# F3DroneV4.net
KiCad netlist of a schematic drawn in Altium Designer
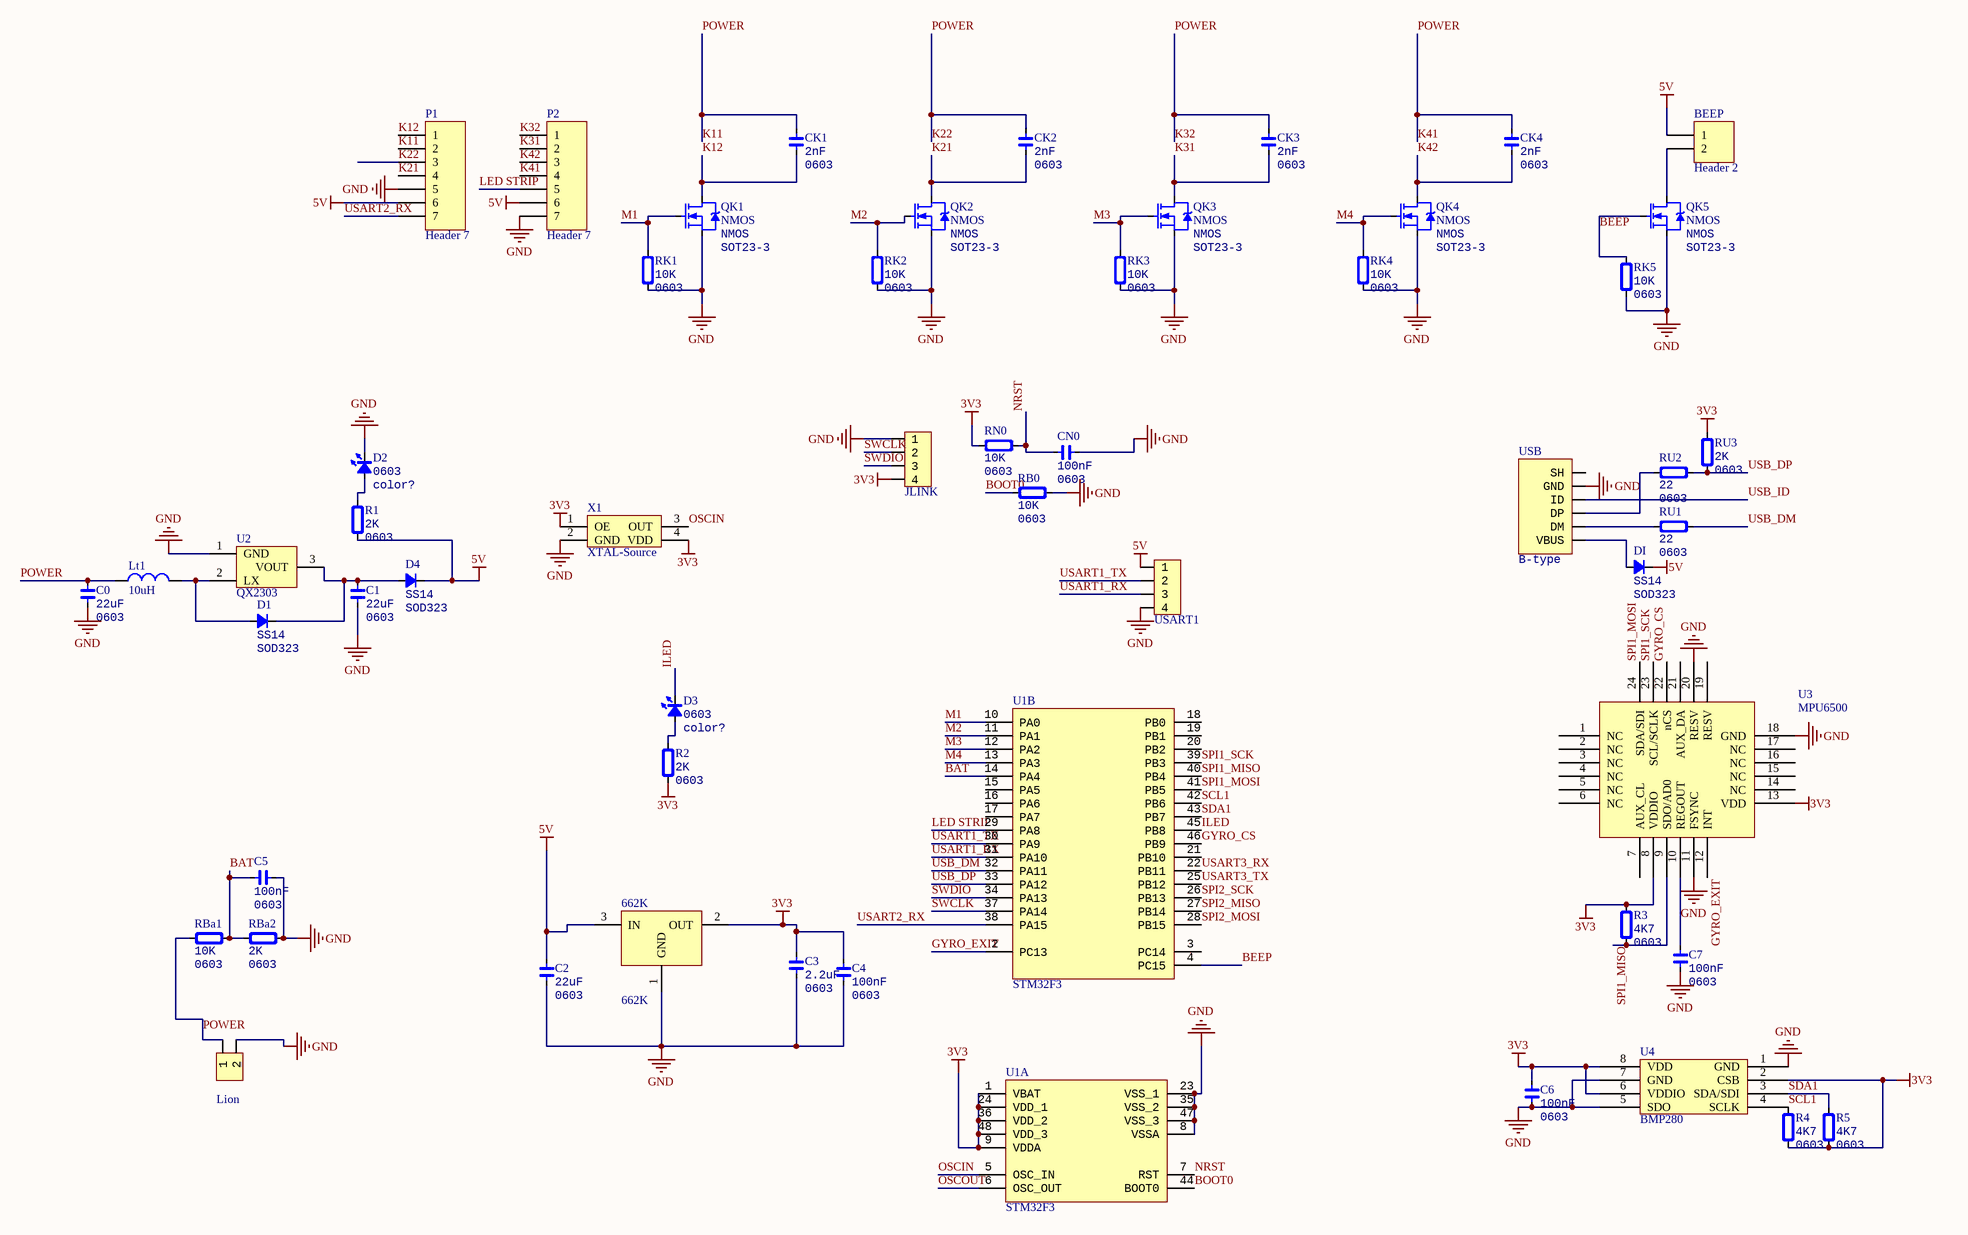
[diagram p0: F3DroneV4.SchDoc]

(export (version "E")
  (design (tool "Eeschema 10.0.6"))
  (components
    (comp (ref "662K") (value "662K") (footprint "SOT-23") (libsource (lib "PPD") (part "662K")))
    (comp (ref "BEEP")
      (value "Header 2")
      (footprint "HDR1X2")
      (description "Header, 2-Pin")
      (fields (field (name "PUBLISHER") "Altium Limited"))
      (libsource (lib "Miscellaneous Connectors") (part "Header 2"))
    )
    (comp (ref "C0")
      (value "22uF")
      (footprint "CAP_0603")
      (description "Capacitor")
      (fields (field (name "TYPE") "0603") (field (name "Comment") "C0603"))
      (libsource (lib "Integrated_Library") (part "Cap_0603"))
    )
    (comp (ref "C1")
      (value "22uF")
      (footprint "CAP_0603")
      (description "Capacitor")
      (fields (field (name "TYPE") "0603") (field (name "Comment") "C0603"))
      (libsource (lib "Integrated_Library") (part "Cap_0603"))
    )
    (comp (ref "C2")
      (value "22uF")
      (footprint "CAP_0603")
      (description "Capacitor")
      (fields (field (name "TYPE") "0603") (field (name "Comment") "C0603"))
      (libsource (lib "Integrated_Library") (part "Cap_0603"))
    )
    (comp (ref "C3")
      (value "2.2uF")
      (footprint "CAP_0603")
      (description "Capacitor")
      (fields (field (name "TYPE") "0603") (field (name "Comment") "C0603"))
      (libsource (lib "Integrated_Library") (part "Cap_0603"))
    )
    (comp (ref "C4")
      (value "100nF")
      (footprint "CAP_0603")
      (description "Capacitor")
      (fields (field (name "TYPE") "0603") (field (name "Comment") "C0603"))
      (libsource (lib "Integrated_Library") (part "Cap_0603"))
    )
    (comp (ref "C5")
      (value "100nF")
      (footprint "CAP_0603")
      (description "Capacitor")
      (fields (field (name "TYPE") "0603") (field (name "Comment") "C0603"))
      (libsource (lib "") (part "Cap_0603_1"))
    )
    (comp (ref "C6")
      (value "100nF")
      (footprint "CAP_0603")
      (description "Capacitor")
      (fields (field (name "TYPE") "0603") (field (name "Comment") "C0603"))
      (libsource (lib "") (part "Cap_0603_2"))
    )
    (comp (ref "C7")
      (value "100nF")
      (footprint "CAP_0603")
      (description "Capacitor")
      (fields (field (name "TYPE") "0603") (field (name "Comment") "C0603"))
      (libsource (lib "") (part "Cap_0603_2"))
    )
    (comp (ref "CK1")
      (value "2nF")
      (footprint "CAP_0603")
      (description "Capacitor")
      (fields (field (name "TYPE") "0603") (field (name "Comment") "C0603"))
      (libsource (lib "Integrated_Library") (part "Cap_0603"))
    )
    (comp (ref "CK2")
      (value "2nF")
      (footprint "CAP_0603")
      (description "Capacitor")
      (fields (field (name "TYPE") "0603") (field (name "Comment") "C0603"))
      (libsource (lib "Integrated_Library") (part "Cap_0603"))
    )
    (comp (ref "CK3")
      (value "2nF")
      (footprint "CAP_0603")
      (description "Capacitor")
      (fields (field (name "TYPE") "0603") (field (name "Comment") "C0603"))
      (libsource (lib "Integrated_Library") (part "Cap_0603"))
    )
    (comp (ref "CK4")
      (value "2nF")
      (footprint "CAP_0603")
      (description "Capacitor")
      (fields (field (name "TYPE") "0603") (field (name "Comment") "C0603"))
      (libsource (lib "Integrated_Library") (part "Cap_0603"))
    )
    (comp (ref "CN0")
      (value "100nF")
      (footprint "CAP_0603")
      (description "Capacitor")
      (fields (field (name "TYPE") "0603") (field (name "Comment") "C0603"))
      (libsource (lib "") (part "Cap_0603_1"))
    )
    (comp (ref "D1")
      (value "SS14")
      (footprint "SOD-323")
      (description "Diode")
      (fields (field (name "TYPE") "SOD323"))
      (libsource (lib "Integrated_Library") (part "Diode_SOD323"))
    )
    (comp (ref "D2")
      (value "color?")
      (footprint "LED_0603_BLUE")
      (description "LED")
      (fields (field (name "TYPE") "0603"))
      (libsource (lib "Integrated_Library") (part "LED_0603"))
    )
    (comp (ref "D3")
      (value "color?")
      (footprint "LED_0603_BLUE")
      (description "LED")
      (fields (field (name "TYPE") "0603"))
      (libsource (lib "Integrated_Library") (part "LED_0603"))
    )
    (comp (ref "D4")
      (value "SS14")
      (footprint "SOD-323")
      (description "Diode")
      (fields (field (name "TYPE") "SOD323"))
      (libsource (lib "Integrated_Library") (part "Diode_SOD323"))
    )
    (comp (ref "DI")
      (value "SS14")
      (footprint "SOD-323")
      (description "Diode")
      (fields (field (name "TYPE") "SOD323"))
      (libsource (lib "Integrated_Library") (part "Diode_SOD323"))
    )
    (comp (ref "JLINK")
      (value "HDR1x4_1.27")
      (footprint "HDR1X4_1.27_180")
      (description "Header")
      (libsource (lib "Integrated_Library") (part "HDR1x4_1.27"))
    )
    (comp (ref "Lion")
      (value "HDR1x2_1.27T")
      (footprint "HDR1X2_1.27_180")
      (description "Header")
      (libsource (lib "Integrated_Library") (part "HDR1x2_1.27T"))
    )
    (comp (ref "Lt1")
      (value "10uH")
      (footprint "0420")
      (description "电感")
      (fields (field (name "Comment") "Inductor") (field (name "PUBLISHER") "Altium Limited"))
      (libsource (lib "PPD") (part "Inductor"))
    )
    (comp (ref "P1")
      (value "Header 7")
      (footprint "HDR1X7")
      (description "Header, 7-Pin")
      (fields (field (name "PUBLISHER") "Altium Limited"))
      (libsource (lib "Miscellaneous Connectors") (part "Header 7"))
    )
    (comp (ref "P2")
      (value "Header 7")
      (footprint "HDR1X7")
      (description "Header, 7-Pin")
      (fields (field (name "PUBLISHER") "Altium Limited"))
      (libsource (lib "Miscellaneous Connectors") (part "Header 7"))
    )
    (comp (ref "QK1")
      (value "NMOS")
      (footprint "SOT23-3")
      (description "MOSFET")
      (fields (field (name "ALTIUM_VALUE") "NMOS") (field (name "TYPE") "SOT23-3"))
      (libsource (lib "Integrated_Library") (part "MOSFET_N_SOT23"))
    )
    (comp (ref "QK2")
      (value "NMOS")
      (footprint "SOT23-3")
      (description "MOSFET")
      (fields (field (name "ALTIUM_VALUE") "NMOS") (field (name "TYPE") "SOT23-3"))
      (libsource (lib "Integrated_Library") (part "MOSFET_N_SOT23"))
    )
    (comp (ref "QK3")
      (value "NMOS")
      (footprint "SOT23-3")
      (description "MOSFET")
      (fields (field (name "ALTIUM_VALUE") "NMOS") (field (name "TYPE") "SOT23-3"))
      (libsource (lib "Integrated_Library") (part "MOSFET_N_SOT23"))
    )
    (comp (ref "QK4")
      (value "NMOS")
      (footprint "SOT23-3")
      (description "MOSFET")
      (fields (field (name "ALTIUM_VALUE") "NMOS") (field (name "TYPE") "SOT23-3"))
      (libsource (lib "Integrated_Library") (part "MOSFET_N_SOT23"))
    )
    (comp (ref "QK5")
      (value "NMOS")
      (footprint "SOT23-3")
      (description "MOSFET")
      (fields (field (name "ALTIUM_VALUE") "NMOS") (field (name "TYPE") "SOT23-3"))
      (libsource (lib "Integrated_Library") (part "MOSFET_N_SOT23"))
    )
    (comp (ref "R1")
      (value "2K")
      (footprint "RES_0603")
      (description "Resistor")
      (fields (field (name "TYPE") "0603") (field (name "Comment") "R0603"))
      (libsource (lib "Integrated_Library") (part "Res_0603"))
    )
    (comp (ref "R2")
      (value "2K")
      (footprint "RES_0603")
      (description "Resistor")
      (fields (field (name "TYPE") "0603") (field (name "Comment") "R0603"))
      (libsource (lib "Integrated_Library") (part "Res_0603"))
    )
    (comp (ref "R3")
      (value "4K7")
      (footprint "RES_0603")
      (description "Resistor")
      (fields (field (name "TYPE") "0603") (field (name "Comment") "R0603"))
      (libsource (lib "Integrated_Library") (part "Res_0603"))
    )
    (comp (ref "R4")
      (value "4K7")
      (footprint "RES_0603")
      (description "Resistor")
      (fields (field (name "TYPE") "0603") (field (name "Comment") "R0603"))
      (libsource (lib "Integrated_Library") (part "Res_0603"))
    )
    (comp (ref "R5")
      (value "4K7")
      (footprint "RES_0603")
      (description "Resistor")
      (fields (field (name "TYPE") "0603") (field (name "Comment") "R0603"))
      (libsource (lib "Integrated_Library") (part "Res_0603"))
    )
    (comp (ref "RB0")
      (value "10K")
      (footprint "RES_0603")
      (description "Resistor")
      (fields (field (name "TYPE") "0603") (field (name "Comment") "R0603"))
      (libsource (lib "Integrated_Library") (part "Res_0603"))
    )
    (comp (ref "RBa1")
      (value "10K")
      (footprint "RES_0603")
      (description "Resistor")
      (fields (field (name "TYPE") "0603") (field (name "Comment") "R0603"))
      (libsource (lib "Integrated_Library") (part "Res_0603"))
    )
    (comp (ref "RBa2")
      (value "2K")
      (footprint "RES_0603")
      (description "Resistor")
      (fields (field (name "TYPE") "0603") (field (name "Comment") "R0603"))
      (libsource (lib "Integrated_Library") (part "Res_0603"))
    )
    (comp (ref "RK1")
      (value "10K")
      (footprint "RES_0603")
      (description "Resistor")
      (fields (field (name "TYPE") "0603") (field (name "Comment") "R0603"))
      (libsource (lib "Integrated_Library") (part "Res_0603"))
    )
    (comp (ref "RK2")
      (value "10K")
      (footprint "RES_0603")
      (description "Resistor")
      (fields (field (name "TYPE") "0603") (field (name "Comment") "R0603"))
      (libsource (lib "Integrated_Library") (part "Res_0603"))
    )
    (comp (ref "RK3")
      (value "10K")
      (footprint "RES_0603")
      (description "Resistor")
      (fields (field (name "TYPE") "0603") (field (name "Comment") "R0603"))
      (libsource (lib "Integrated_Library") (part "Res_0603"))
    )
    (comp (ref "RK4")
      (value "10K")
      (footprint "RES_0603")
      (description "Resistor")
      (fields (field (name "TYPE") "0603") (field (name "Comment") "R0603"))
      (libsource (lib "Integrated_Library") (part "Res_0603"))
    )
    (comp (ref "RK5")
      (value "10K")
      (footprint "RES_0603")
      (description "Resistor")
      (fields (field (name "TYPE") "0603") (field (name "Comment") "R0603"))
      (libsource (lib "Integrated_Library") (part "Res_0603"))
    )
    (comp (ref "RN0")
      (value "10K")
      (footprint "RES_0603")
      (description "Resistor")
      (fields (field (name "TYPE") "0603") (field (name "Comment") "R0603"))
      (libsource (lib "Integrated_Library") (part "Res_0603"))
    )
    (comp (ref "RU1")
      (value "22")
      (footprint "RES_0603")
      (description "Resistor")
      (fields (field (name "TYPE") "0603") (field (name "Comment") "R0603"))
      (libsource (lib "Integrated_Library") (part "Res_0603"))
    )
    (comp (ref "RU2")
      (value "22")
      (footprint "RES_0603")
      (description "Resistor")
      (fields (field (name "TYPE") "0603") (field (name "Comment") "R0603"))
      (libsource (lib "Integrated_Library") (part "Res_0603"))
    )
    (comp (ref "RU3")
      (value "2K")
      (footprint "RES_0603")
      (description "Resistor")
      (fields (field (name "TYPE") "0603") (field (name "Comment") "R0603"))
      (libsource (lib "Integrated_Library") (part "Res_0603"))
    )
    (comp (ref "U1")
      (value "STM32F3")
      (footprint "LQFP_P0.5_48")
      (description "MCU")
      (libsource (lib "Integrated_Library") (part "STM32F303C"))
    )
    (comp (ref "U2") (value "QX2303") (footprint "SOT-23") (libsource (lib "PPD") (part "QX2303")))
    (comp (ref "U3")
      (value "MPU6500")
      (footprint "QFN40P300X300X90_HS-25N")
      (libsource (lib "PPD") (part "MPU6500"))
    )
    (comp (ref "U4") (value "BMP280") (footprint "BMP280") (libsource (lib "PPD") (part "BMP280")))
    (comp (ref "USART1")
      (value "HDR1x4_1.27")
      (footprint "HDR1X4_1.27_180")
      (description "Header")
      (libsource (lib "Integrated_Library") (part "HDR1x4_1.27"))
    )
    (comp (ref "USB")
      (value "MicroUSB")
      (footprint "USB_Micro-AB")
      (description "USB")
      (fields (field (name "TYPE") "B-type"))
      (libsource (lib "Integrated_Library") (part "USB_Micro"))
    )
    (comp (ref "X1")
      (value "XTAL-Source")
      (footprint "XTAL_3225")
      (libsource (lib "PPD") (part "XTAL-Source"))
    )
  )
  (nets
    (net (code "1") (name "/BAT") (class "Default")
      (node (ref "C5") (pin "2") (pinfunction "2_2") (pintype "passive"))
      (node (ref "RBa1") (pin "1") (pinfunction "1_1") (pintype "passive"))
      (node (ref "RBa2") (pin "2") (pinfunction "2_2") (pintype "passive"))
      (node (ref "U1") (pin "14") (pinfunction "PA4_14") (pintype "passive"))
    )
    (net (code "2") (name "/BEEP") (class "Default")
      (node (ref "QK5") (pin "1") (pinfunction "G_1") (pintype "passive"))
      (node (ref "RK5") (pin "2") (pinfunction "2_2") (pintype "passive"))
      (node (ref "U1") (pin "4") (pinfunction "PC15_4") (pintype "passive"))
    )
    (net (code "3") (name "/BOOT0") (class "Default")
      (node (ref "RB0") (pin "2") (pinfunction "2_2") (pintype "passive"))
      (node (ref "U1") (pin "44") (pinfunction "BOOT0_44") (pintype "passive"))
    )
    (net (code "4") (name "/GYRO_CS") (class "Default")
      (node (ref "U1") (pin "46") (pinfunction "PB9_46") (pintype "passive"))
      (node (ref "U3") (pin "22") (pinfunction "nCS_22") (pintype "passive"))
    )
    (net (code "5") (name "/GYRO_EXIT") (class "Default")
      (node (ref "U1") (pin "2") (pinfunction "PC13_2") (pintype "passive"))
      (node (ref "U3") (pin "12") (pinfunction "INT_12") (pintype "passive"))
    )
    (net (code "6") (name "/ILED") (class "Default")
      (node (ref "D3") (pin "2") (pinfunction "K_2") (pintype "passive"))
      (node (ref "U1") (pin "45") (pinfunction "PB8_45") (pintype "passive"))
    )
    (net (code "7") (name "/K11") (class "Default")
      (node (ref "C0") (pin "2") (pinfunction "2_2") (pintype "passive"))
      (node (ref "CK1") (pin "2") (pinfunction "2_2") (pintype "passive"))
      (node (ref "CK2") (pin "2") (pinfunction "2_2") (pintype "passive"))
      (node (ref "CK3") (pin "2") (pinfunction "2_2") (pintype "passive"))
      (node (ref "CK4") (pin "2") (pinfunction "2_2") (pintype "passive"))
      (node (ref "Lion") (pin "1") (pinfunction "1_1") (pintype "passive"))
      (node (ref "Lt1") (pin "1") (pinfunction "1_1") (pintype "passive"))
      (node (ref "P1") (pin "2") (pinfunction "2_2") (pintype "passive"))
      (node (ref "P1") (pin "3") (pinfunction "3_3") (pintype "passive"))
      (node (ref "P2") (pin "1") (pinfunction "1_1") (pintype "passive"))
      (node (ref "P2") (pin "4") (pinfunction "4_4") (pintype "passive"))
      (node (ref "RBa1") (pin "2") (pinfunction "2_2") (pintype "passive"))
    )
    (net (code "8") (name "/K12") (class "Default")
      (node (ref "CK1") (pin "1") (pinfunction "1_1") (pintype "passive"))
      (node (ref "P1") (pin "1") (pinfunction "1_1") (pintype "passive"))
      (node (ref "QK1") (pin "3") (pinfunction "D_3") (pintype "passive"))
    )
    (net (code "9") (name "/K21") (class "Default")
      (node (ref "CK2") (pin "1") (pinfunction "1_1") (pintype "passive"))
      (node (ref "P1") (pin "4") (pinfunction "4_4") (pintype "passive"))
      (node (ref "QK2") (pin "3") (pinfunction "D_3") (pintype "passive"))
    )
    (net (code "10") (name "/K31") (class "Default")
      (node (ref "CK3") (pin "1") (pinfunction "1_1") (pintype "passive"))
      (node (ref "P2") (pin "2") (pinfunction "2_2") (pintype "passive"))
      (node (ref "QK3") (pin "3") (pinfunction "D_3") (pintype "passive"))
    )
    (net (code "11") (name "/K42") (class "Default")
      (node (ref "CK4") (pin "1") (pinfunction "1_1") (pintype "passive"))
      (node (ref "P2") (pin "3") (pinfunction "3_3") (pintype "passive"))
      (node (ref "QK4") (pin "3") (pinfunction "D_3") (pintype "passive"))
    )
    (net (code "12") (name "/LED STRIP") (class "Default")
      (node (ref "P2") (pin "5") (pinfunction "5_5") (pintype "passive"))
      (node (ref "U1") (pin "29") (pinfunction "PA8_29") (pintype "passive"))
    )
    (net (code "13") (name "/M1") (class "Default")
      (node (ref "QK1") (pin "1") (pinfunction "G_1") (pintype "passive"))
      (node (ref "RK1") (pin "2") (pinfunction "2_2") (pintype "passive"))
      (node (ref "U1") (pin "10") (pinfunction "PA0_10") (pintype "passive"))
    )
    (net (code "14") (name "/M2") (class "Default")
      (node (ref "QK2") (pin "1") (pinfunction "G_1") (pintype "passive"))
      (node (ref "RK2") (pin "2") (pinfunction "2_2") (pintype "passive"))
      (node (ref "U1") (pin "11") (pinfunction "PA1_11") (pintype "passive"))
    )
    (net (code "15") (name "/M3") (class "Default")
      (node (ref "QK3") (pin "1") (pinfunction "G_1") (pintype "passive"))
      (node (ref "RK3") (pin "2") (pinfunction "2_2") (pintype "passive"))
      (node (ref "U1") (pin "12") (pinfunction "PA2_12") (pintype "passive"))
    )
    (net (code "16") (name "/M4") (class "Default")
      (node (ref "QK4") (pin "1") (pinfunction "G_1") (pintype "passive"))
      (node (ref "RK4") (pin "2") (pinfunction "2_2") (pintype "passive"))
      (node (ref "U1") (pin "13") (pinfunction "PA3_13") (pintype "passive"))
    )
    (net (code "17") (name "/NRST") (class "Default")
      (node (ref "CN0") (pin "2") (pinfunction "2_2") (pintype "passive"))
      (node (ref "RN0") (pin "1") (pinfunction "1_1") (pintype "passive"))
      (node (ref "U1") (pin "7") (pinfunction "RST_7") (pintype "passive"))
    )
    (net (code "18") (name "/OSCIN") (class "Default")
      (node (ref "U1") (pin "5") (pinfunction "OSC_IN_5") (pintype "passive"))
      (node (ref "X1") (pin "3") (pinfunction "OUT_3") (pintype "passive"))
    )
    (net (code "19") (name "/OSCOUT") (class "Default")
      (node (ref "U1") (pin "6") (pinfunction "OSC_OUT_6") (pintype "passive"))
    )
    (net (code "20") (name "/SCL1") (class "Default")
      (node (ref "R4") (pin "2") (pinfunction "2_2") (pintype "passive"))
      (node (ref "U1") (pin "42") (pinfunction "PB6_42") (pintype "passive"))
      (node (ref "U4") (pin "4") (pinfunction "SCLK_4") (pintype "passive"))
    )
    (net (code "21") (name "/SDA1") (class "Default")
      (node (ref "R5") (pin "2") (pinfunction "2_2") (pintype "passive"))
      (node (ref "U1") (pin "43") (pinfunction "PB7_43") (pintype "passive"))
      (node (ref "U4") (pin "3") (pinfunction "SDA/SDI_3") (pintype "passive"))
    )
    (net (code "22") (name "/SPI1_MISO") (class "Default")
      (node (ref "R3") (pin "1") (pinfunction "1_1") (pintype "passive"))
      (node (ref "U1") (pin "40") (pinfunction "PB4_40") (pintype "passive"))
      (node (ref "U3") (pin "9") (pinfunction "SDO/AD0_9") (pintype "passive"))
    )
    (net (code "23") (name "/SPI1_MOSI") (class "Default")
      (node (ref "U1") (pin "41") (pinfunction "PB5_41") (pintype "passive"))
      (node (ref "U3") (pin "24") (pinfunction "SDA/SDI_24") (pintype "passive"))
    )
    (net (code "24") (name "/SPI1_SCK") (class "Default")
      (node (ref "U1") (pin "39") (pinfunction "PB3_39") (pintype "passive"))
      (node (ref "U3") (pin "23") (pinfunction "SCL/SCLK_23") (pintype "passive"))
    )
    (net (code "25") (name "/SPI2_MISO") (class "Default")
      (node (ref "U1") (pin "27") (pinfunction "PB14_27") (pintype "passive"))
    )
    (net (code "26") (name "/SPI2_MOSI") (class "Default")
      (node (ref "U1") (pin "28") (pinfunction "PB15_28") (pintype "passive"))
    )
    (net (code "27") (name "/SPI2_SCK") (class "Default")
      (node (ref "U1") (pin "26") (pinfunction "PB13_26") (pintype "passive"))
    )
    (net (code "28") (name "/SWCLK") (class "Default")
      (node (ref "JLINK") (pin "2") (pinfunction "2_2") (pintype "passive"))
      (node (ref "U1") (pin "37") (pinfunction "PA14_37") (pintype "passive"))
    )
    (net (code "29") (name "/SWDIO") (class "Default")
      (node (ref "JLINK") (pin "3") (pinfunction "3_3") (pintype "passive"))
      (node (ref "U1") (pin "34") (pinfunction "PA13_34") (pintype "passive"))
    )
    (net (code "30") (name "/USART1_RX") (class "Default")
      (node (ref "U1") (pin "31") (pinfunction "PA10_31") (pintype "passive"))
      (node (ref "USART1") (pin "3") (pinfunction "3_3") (pintype "passive"))
    )
    (net (code "31") (name "/USART1_TX") (class "Default")
      (node (ref "U1") (pin "30") (pinfunction "PA9_30") (pintype "passive"))
      (node (ref "USART1") (pin "2") (pinfunction "2_2") (pintype "passive"))
    )
    (net (code "32") (name "/USART2_RX") (class "Default")
      (node (ref "P1") (pin "7") (pinfunction "7_7") (pintype "passive"))
      (node (ref "U1") (pin "38") (pinfunction "PA15_38") (pintype "passive"))
    )
    (net (code "33") (name "/USART3_RX") (class "Default")
      (node (ref "U1") (pin "22") (pinfunction "PB11_22") (pintype "passive"))
    )
    (net (code "34") (name "/USART3_TX") (class "Default")
      (node (ref "U1") (pin "25") (pinfunction "PB12_25") (pintype "passive"))
    )
    (net (code "35") (name "/USB_DM") (class "Default")
      (node (ref "RU1") (pin "1") (pinfunction "1_1") (pintype "passive"))
      (node (ref "U1") (pin "32") (pinfunction "PA11_32") (pintype "passive"))
    )
    (net (code "36") (name "/USB_DP") (class "Default")
      (node (ref "RU2") (pin "1") (pinfunction "1_1") (pintype "passive"))
      (node (ref "RU3") (pin "2") (pinfunction "2_2") (pintype "passive"))
      (node (ref "U1") (pin "33") (pinfunction "PA12_33") (pintype "passive"))
    )
    (net (code "37") (name "/USB_ID") (class "Default")
      (node (ref "USB") (pin "4") (pinfunction "ID_4") (pintype "passive"))
    )
    (net (code "38") (name "3V3") (class "Default")
      (node (ref "662K") (pin "2") (pinfunction "OUT_2") (pintype "passive"))
      (node (ref "C3") (pin "2") (pinfunction "2_2") (pintype "passive"))
      (node (ref "C4") (pin "2") (pinfunction "2_2") (pintype "passive"))
      (node (ref "C6") (pin "1") (pinfunction "1_1") (pintype "passive"))
      (node (ref "JLINK") (pin "4") (pinfunction "4_4") (pintype "passive"))
      (node (ref "R2") (pin "1") (pinfunction "1_1") (pintype "passive"))
      (node (ref "R3") (pin "2") (pinfunction "2_2") (pintype "passive"))
      (node (ref "R4") (pin "1") (pinfunction "1_1") (pintype "passive"))
      (node (ref "R5") (pin "1") (pinfunction "1_1") (pintype "passive"))
      (node (ref "RN0") (pin "2") (pinfunction "2_2") (pintype "passive"))
      (node (ref "RU3") (pin "1") (pinfunction "1_1") (pintype "passive"))
      (node (ref "U1") (pin "1") (pinfunction "VBAT_1") (pintype "passive"))
      (node (ref "U1") (pin "24") (pinfunction "VDD_1_24") (pintype "passive"))
      (node (ref "U1") (pin "36") (pinfunction "VDD_2_36") (pintype "passive"))
      (node (ref "U1") (pin "48") (pinfunction "VDD_3_48") (pintype "passive"))
      (node (ref "U1") (pin "9") (pinfunction "VDDA_9") (pintype "passive"))
      (node (ref "U3") (pin "13") (pinfunction "VDD_13") (pintype "passive"))
      (node (ref "U3") (pin "8") (pinfunction "VDDIO_8") (pintype "passive"))
      (node (ref "U4") (pin "2") (pinfunction "CSB_2") (pintype "passive"))
      (node (ref "U4") (pin "6") (pinfunction "VDDIO_6") (pintype "passive"))
      (node (ref "U4") (pin "8") (pinfunction "VDD_8") (pintype "passive"))
      (node (ref "X1") (pin "1") (pinfunction "OE_1") (pintype "passive"))
      (node (ref "X1") (pin "4") (pinfunction "VDD_4") (pintype "passive"))
    )
    (net (code "39") (name "5V") (class "Default")
      (node (ref "662K") (pin "3") (pinfunction "IN_3") (pintype "passive"))
      (node (ref "BEEP") (pin "1") (pinfunction "1_1") (pintype "passive"))
      (node (ref "C2") (pin "2") (pinfunction "2_2") (pintype "passive"))
      (node (ref "D4") (pin "2") (pinfunction "K_2") (pintype "passive"))
      (node (ref "DI") (pin "2") (pinfunction "K_2") (pintype "passive"))
      (node (ref "P1") (pin "6") (pinfunction "6_6") (pintype "passive"))
      (node (ref "P2") (pin "6") (pinfunction "6_6") (pintype "passive"))
      (node (ref "R1") (pin "1") (pinfunction "1_1") (pintype "passive"))
      (node (ref "USART1") (pin "1") (pinfunction "1_1") (pintype "passive"))
    )
    (net (code "40") (name "GND") (class "Default")
      (node (ref "662K") (pin "1") (pinfunction "GND_1") (pintype "passive"))
      (node (ref "C0") (pin "1") (pinfunction "1_1") (pintype "passive"))
      (node (ref "C1") (pin "1") (pinfunction "1_1") (pintype "passive"))
      (node (ref "C2") (pin "1") (pinfunction "1_1") (pintype "passive"))
      (node (ref "C3") (pin "1") (pinfunction "1_1") (pintype "passive"))
      (node (ref "C4") (pin "1") (pinfunction "1_1") (pintype "passive"))
      (node (ref "C5") (pin "1") (pinfunction "1_1") (pintype "passive"))
      (node (ref "C6") (pin "2") (pinfunction "2_2") (pintype "passive"))
      (node (ref "C7") (pin "2") (pinfunction "2_2") (pintype "passive"))
      (node (ref "CN0") (pin "1") (pinfunction "1_1") (pintype "passive"))
      (node (ref "D2") (pin "2") (pinfunction "K_2") (pintype "passive"))
      (node (ref "JLINK") (pin "1") (pinfunction "1_1") (pintype "passive"))
      (node (ref "Lion") (pin "2") (pinfunction "2_2") (pintype "passive"))
      (node (ref "P1") (pin "5") (pinfunction "5_5") (pintype "passive"))
      (node (ref "P2") (pin "7") (pinfunction "7_7") (pintype "passive"))
      (node (ref "QK1") (pin "2") (pinfunction "S_2") (pintype "passive"))
      (node (ref "QK2") (pin "2") (pinfunction "S_2") (pintype "passive"))
      (node (ref "QK3") (pin "2") (pinfunction "S_2") (pintype "passive"))
      (node (ref "QK4") (pin "2") (pinfunction "S_2") (pintype "passive"))
      (node (ref "QK5") (pin "2") (pinfunction "S_2") (pintype "passive"))
      (node (ref "RB0") (pin "1") (pinfunction "1_1") (pintype "passive"))
      (node (ref "RBa2") (pin "1") (pinfunction "1_1") (pintype "passive"))
      (node (ref "RK1") (pin "1") (pinfunction "1_1") (pintype "passive"))
      (node (ref "RK2") (pin "1") (pinfunction "1_1") (pintype "passive"))
      (node (ref "RK3") (pin "1") (pinfunction "1_1") (pintype "passive"))
      (node (ref "RK4") (pin "1") (pinfunction "1_1") (pintype "passive"))
      (node (ref "RK5") (pin "1") (pinfunction "1_1") (pintype "passive"))
      (node (ref "U1") (pin "23") (pinfunction "VSS_1_23") (pintype "passive"))
      (node (ref "U1") (pin "35") (pinfunction "VSS_2_35") (pintype "passive"))
      (node (ref "U1") (pin "47") (pinfunction "VSS_3_47") (pintype "passive"))
      (node (ref "U1") (pin "8") (pinfunction "VSSA_8") (pintype "passive"))
      (node (ref "U2") (pin "1") (pinfunction "GND_1") (pintype "passive"))
      (node (ref "U3") (pin "11") (pinfunction "FSYNC_11") (pintype "passive"))
      (node (ref "U3") (pin "18") (pinfunction "GND_18") (pintype "passive"))
      (node (ref "U3") (pin "20") (pinfunction "RESV_20") (pintype "passive"))
      (node (ref "U4") (pin "1") (pinfunction "GND_1") (pintype "passive"))
      (node (ref "U4") (pin "5") (pinfunction "SDO_5") (pintype "passive"))
      (node (ref "U4") (pin "7") (pinfunction "GND_7") (pintype "passive"))
      (node (ref "USART1") (pin "4") (pinfunction "4_4") (pintype "passive"))
      (node (ref "USB") (pin "5") (pinfunction "GND_5") (pintype "passive"))
      (node (ref "X1") (pin "2") (pinfunction "GND_2") (pintype "passive"))
    )
    (net (code "41") (name "Net-(D1-A)") (class "Default")
      (node (ref "D1") (pin "1") (pinfunction "A_1") (pintype "passive"))
      (node (ref "Lt1") (pin "2") (pinfunction "2_2") (pintype "passive"))
      (node (ref "U2") (pin "2") (pinfunction "LX_2") (pintype "passive"))
    )
    (net (code "42") (name "Net-(D1-K)") (class "Default")
      (node (ref "C1") (pin "2") (pinfunction "2_2") (pintype "passive"))
      (node (ref "D1") (pin "2") (pinfunction "K_2") (pintype "passive"))
      (node (ref "D4") (pin "1") (pinfunction "A_1") (pintype "passive"))
      (node (ref "U2") (pin "3") (pinfunction "VOUT_3") (pintype "passive"))
    )
    (net (code "43") (name "Net-(D2-A)") (class "Default")
      (node (ref "D2") (pin "1") (pinfunction "A_1") (pintype "passive"))
      (node (ref "R1") (pin "2") (pinfunction "2_2") (pintype "passive"))
    )
    (net (code "44") (name "Net-(D3-A)") (class "Default")
      (node (ref "D3") (pin "1") (pinfunction "A_1") (pintype "passive"))
      (node (ref "R2") (pin "2") (pinfunction "2_2") (pintype "passive"))
    )
    (net (code "45") (name "Net-(DI-A)") (class "Default")
      (node (ref "DI") (pin "1") (pinfunction "A_1") (pintype "passive"))
      (node (ref "USB") (pin "1") (pinfunction "VBUS_1") (pintype "passive"))
    )
    (net (code "46") (name "Net-(QK5-D)") (class "Default")
      (node (ref "BEEP") (pin "2") (pinfunction "2_2") (pintype "passive"))
      (node (ref "QK5") (pin "3") (pinfunction "D_3") (pintype "passive"))
    )
    (net (code "47") (name "Net-(U3-REGOUT)") (class "Default")
      (node (ref "C7") (pin "1") (pinfunction "1_1") (pintype "passive"))
      (node (ref "U3") (pin "10") (pinfunction "REGOUT_10") (pintype "passive"))
    )
    (net (code "48") (name "Net-(USB-DM)") (class "Default")
      (node (ref "RU1") (pin "2") (pinfunction "2_2") (pintype "passive"))
      (node (ref "USB") (pin "2") (pinfunction "DM_2") (pintype "passive"))
    )
    (net (code "49") (name "Net-(USB-DP)") (class "Default")
      (node (ref "RU2") (pin "2") (pinfunction "2_2") (pintype "passive"))
      (node (ref "USB") (pin "3") (pinfunction "DP_3") (pintype "passive"))
    )
    (net (code "50") (name "unconnected-(U1B-PA5-Pad15)") (class "Default")
      (node (ref "U1") (pin "15") (pinfunction "PA5_15") (pintype "passive"))
    )
    (net (code "51") (name "unconnected-(U1B-PA6-Pad16)") (class "Default")
      (node (ref "U1") (pin "16") (pinfunction "PA6_16") (pintype "passive"))
    )
    (net (code "52") (name "unconnected-(U1B-PA7-Pad17)") (class "Default")
      (node (ref "U1") (pin "17") (pinfunction "PA7_17") (pintype "passive"))
    )
    (net (code "53") (name "unconnected-(U1B-PB0-Pad18)") (class "Default")
      (node (ref "U1") (pin "18") (pinfunction "PB0_18") (pintype "passive"))
    )
    (net (code "54") (name "unconnected-(U1B-PB1-Pad19)") (class "Default")
      (node (ref "U1") (pin "19") (pinfunction "PB1_19") (pintype "passive"))
    )
    (net (code "55") (name "unconnected-(U1B-PB2-Pad20)") (class "Default")
      (node (ref "U1") (pin "20") (pinfunction "PB2_20") (pintype "passive"))
    )
    (net (code "56") (name "unconnected-(U1B-PB10-Pad21)") (class "Default")
      (node (ref "U1") (pin "21") (pinfunction "PB10_21") (pintype "passive"))
    )
    (net (code "57") (name "unconnected-(U1B-PC14-Pad3)") (class "Default")
      (node (ref "U1") (pin "3") (pinfunction "PC14_3") (pintype "passive"))
    )
    (net (code "58") (name "unconnected-(U3-AUX_CL-Pad7)") (class "Default")
      (node (ref "U3") (pin "7") (pinfunction "AUX_CL_7") (pintype "passive"))
    )
    (net (code "59") (name "unconnected-(U3-AUX_DA-Pad21)") (class "Default")
      (node (ref "U3") (pin "21") (pinfunction "AUX_DA_21") (pintype "passive"))
    )
    (net (code "60") (name "unconnected-(U3-NC-Pad1)") (class "Default")
      (node (ref "U3") (pin "1") (pinfunction "NC_1") (pintype "passive"))
    )
    (net (code "61") (name "unconnected-(U3-NC-Pad2)") (class "Default")
      (node (ref "U3") (pin "2") (pinfunction "NC_2") (pintype "passive"))
    )
    (net (code "62") (name "unconnected-(U3-NC-Pad3)") (class "Default")
      (node (ref "U3") (pin "3") (pinfunction "NC_3") (pintype "passive"))
    )
    (net (code "63") (name "unconnected-(U3-NC-Pad4)") (class "Default")
      (node (ref "U3") (pin "4") (pinfunction "NC_4") (pintype "passive"))
    )
    (net (code "64") (name "unconnected-(U3-NC-Pad5)") (class "Default")
      (node (ref "U3") (pin "5") (pinfunction "NC_5") (pintype "passive"))
    )
    (net (code "65") (name "unconnected-(U3-NC-Pad6)") (class "Default")
      (node (ref "U3") (pin "6") (pinfunction "NC_6") (pintype "passive"))
    )
    (net (code "66") (name "unconnected-(U3-NC-Pad14)") (class "Default")
      (node (ref "U3") (pin "14") (pinfunction "NC_14") (pintype "passive"))
    )
    (net (code "67") (name "unconnected-(U3-NC-Pad15)") (class "Default")
      (node (ref "U3") (pin "15") (pinfunction "NC_15") (pintype "passive"))
    )
    (net (code "68") (name "unconnected-(U3-NC-Pad16)") (class "Default")
      (node (ref "U3") (pin "16") (pinfunction "NC_16") (pintype "passive"))
    )
    (net (code "69") (name "unconnected-(U3-NC-Pad17)") (class "Default")
      (node (ref "U3") (pin "17") (pinfunction "NC_17") (pintype "passive"))
    )
    (net (code "70") (name "unconnected-(U3-RESV-Pad19)") (class "Default")
      (node (ref "U3") (pin "19") (pinfunction "RESV_19") (pintype "passive"))
    )
    (net (code "71") (name "unconnected-(USB-SH-Pad0)") (class "Default")
      (node (ref "USB") (pin "0") (pinfunction "SH_0") (pintype "passive"))
    )
  )
)
